# ESP32.net
KiCad netlist of a schematic drawn in Altium Designer
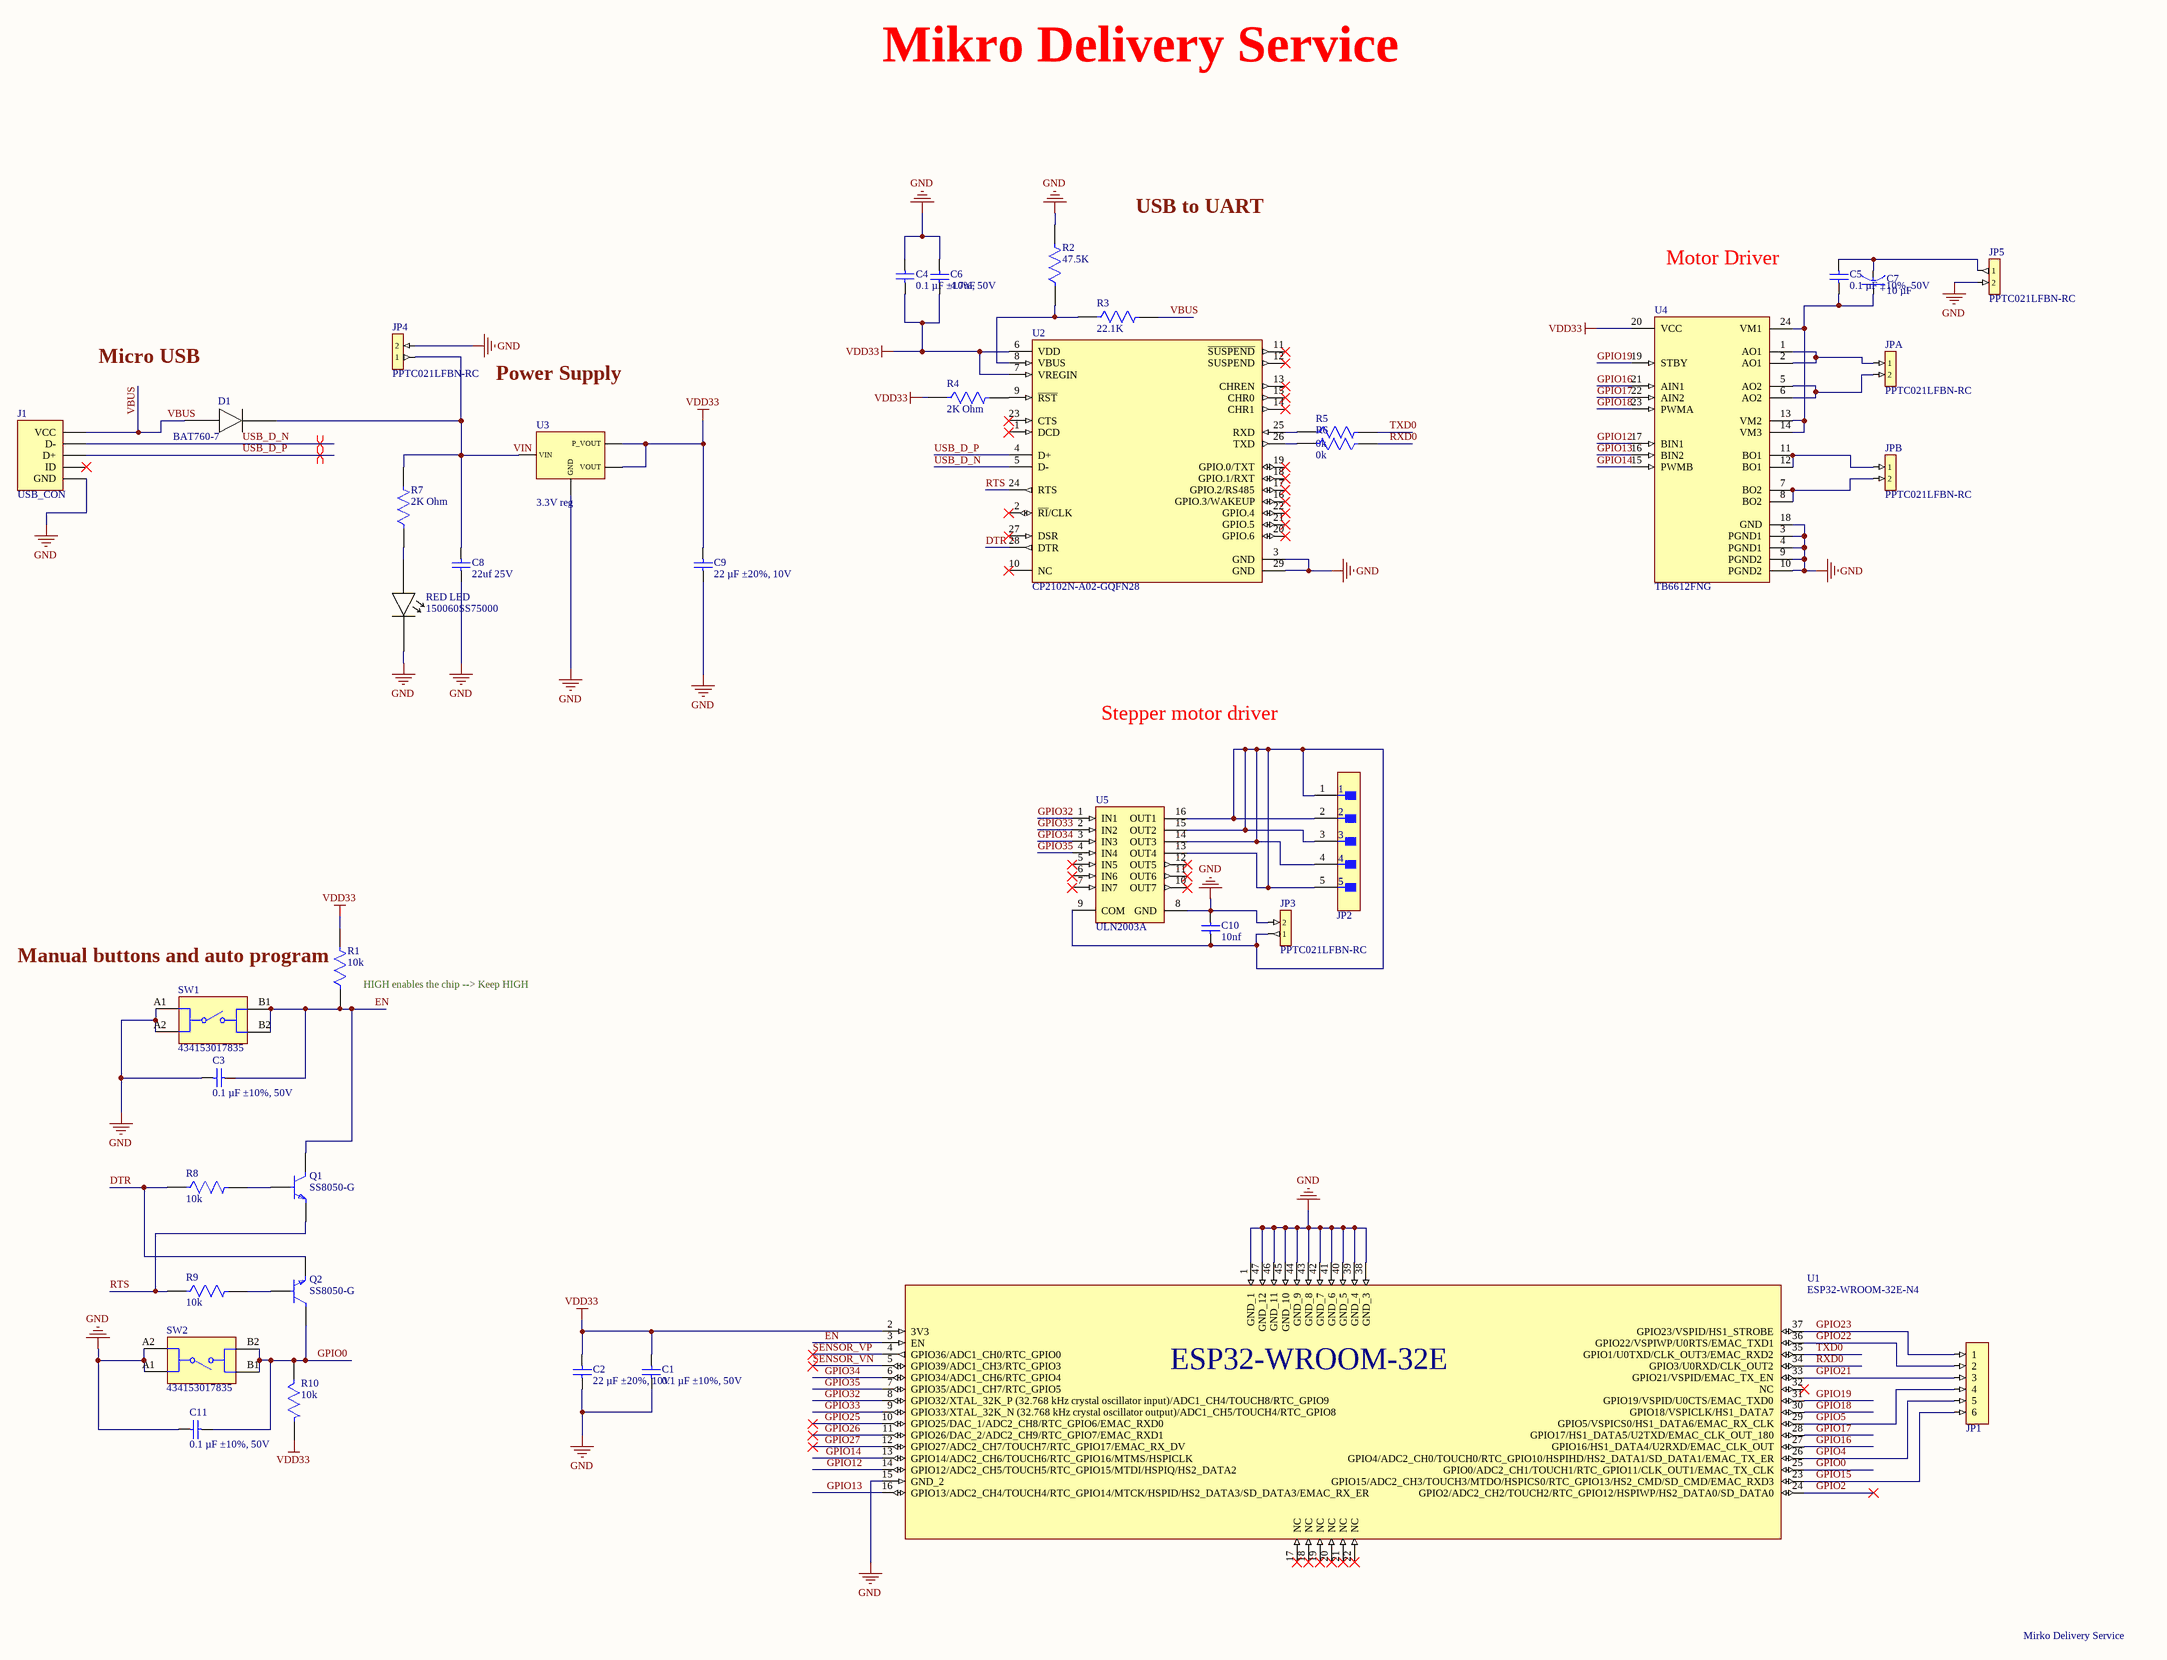
[diagram p0: ESP32.SchDoc]

(export (version "E")
  (design (tool "Eeschema 10.0.6"))
  (components
    (comp (ref "C1")
      (value "0.1 µF ±10%, 50V")
      (footprint "885012206095")
      (description "0.1 µF ±10% 50V Ceramic Capacitor X7R 0603 (1608 Metric)")
      (fields
        (field (name "MANUFACTURER") "Wurth Electronics")
        (field (name "MANUFACTURER PART NUMBER") "885012206095")
      )
      (libsource (lib "Schlib") (part "885012206095"))
    )
    (comp (ref "C2")
      (value "22 µF ±20%, 10V")
      (footprint "885012108011")
      (description "22 µF ±20% 10V Ceramic Capacitor X5R 1206 (3216 Metric)")
      (fields
        (field (name "MANUFACTURER") "Wurth Electronics")
        (field (name "MANUFACTURER PART NUMBER") "885012108011")
      )
      (libsource (lib "Schlib") (part "885012108011"))
    )
    (comp (ref "C3")
      (value "0.1 µF ±10%, 50V")
      (footprint "885012206095")
      (description "0.1 µF ±10% 50V Ceramic Capacitor X7R 0603 (1608 Metric)")
      (fields
        (field (name "MANUFACTURER") "Wurth Electronics")
        (field (name "MANUFACTURER PART NUMBER") "885012206095")
      )
      (libsource (lib "Schlib") (part "885012206095"))
    )
    (comp (ref "C4")
      (value "0.1 µF ±10%, 50V")
      (footprint "885012206095")
      (description "0.1 µF ±10% 50V Ceramic Capacitor X7R 0603 (1608 Metric)")
      (fields
        (field (name "MANUFACTURER") "Wurth Electronics")
        (field (name "MANUFACTURER PART NUMBER") "885012206095")
      )
      (libsource (lib "Schlib") (part "885012206095"))
    )
    (comp (ref "C5")
      (value "0.1 µF ±10%, 50V")
      (footprint "885012206095")
      (description "0.1 µF ±10% 50V Ceramic Capacitor X7R 0603 (1608 Metric)")
      (fields
        (field (name "MANUFACTURER") "Wurth Electronics")
        (field (name "MANUFACTURER PART NUMBER") "885012206095")
      )
      (libsource (lib "Schlib") (part "885012206095"))
    )
    (comp (ref "C6")
      (value "4.7uF")
      (footprint "FP-C0805C475J4RACAUTO-IPC_B")
      (description "4.7 µF ±5% 16V Ceramic Capacitor X7R 0805 (2012 Metric)")
      (fields
        (field (name "MANUFACTURER") "KEMET")
        (field (name "MANUFACTURER PART NUMBER") "C0805C475J4RACAUTO")
      )
      (libsource (lib "Schlib") (part "C0805C475J4RACAUTO"))
    )
    (comp (ref "C7")
      (value "10 µF")
      (footprint "FP-UWT1C100MCL1GB-MFG")
      (description "10 µF 16 V Aluminum Electrolytic Capacitors Radial, Can - SMD 1000 Hrs @ 105°C")
      (fields
        (field (name "MANUFACTURER") "Nichicon")
        (field (name "MANUFACTURER PART NUMBER") "UWT1C100MCL1GB")
      )
      (libsource (lib "Schlib") (part "UWT1C100MCL1GB"))
    )
    (comp (ref "C8")
      (value "22uf 25V")
      (footprint "CL31A226KAHNNNE")
      (description "22 µF ±10% 25V Ceramic Capacitor X5R 1206 (3216 Metric)")
      (fields
        (field (name "MANUFACTURER") "Samsung")
        (field (name "MANUFACTURER PART NUMBER") "CL31A226KAHNNNE")
      )
      (libsource (lib "Schlib") (part "CL31A226KAHNNNE"))
    )
    (comp (ref "C9")
      (value "22 µF ±20%, 10V")
      (footprint "885012108011")
      (description "22 µF ±20% 10V Ceramic Capacitor X5R 1206 (3216 Metric)")
      (fields
        (field (name "MANUFACTURER") "Wurth Electronics")
        (field (name "MANUFACTURER PART NUMBER") "885012108011")
      )
      (libsource (lib "Schlib") (part "885012108011"))
    )
    (comp (ref "C10")
      (value "10nf")
      (footprint "C0402C103K3REC7411")
      (description "10 nF ±10% 25V Ceramic Capacitor X7R 0402 (1005 Metric)")
      (fields
        (field (name "MANUFACTURER") "KEMET")
        (field (name "MANUFACTURER PART NUMBER") "C0402C103K3REC7411")
      )
      (libsource (lib "Schlib") (part "C0402C103K3REC7411"))
    )
    (comp (ref "C11")
      (value "0.1 µF ±10%, 50V")
      (footprint "885012206095")
      (description "0.1 µF ±10% 50V Ceramic Capacitor X7R 0603 (1608 Metric)")
      (fields
        (field (name "MANUFACTURER") "Wurth Electronics")
        (field (name "MANUFACTURER PART NUMBER") "885012206095")
      )
      (libsource (lib "Schlib") (part "885012206095"))
    )
    (comp (ref "D1")
      (value "BAT760-7")
      (footprint "BAT760-7")
      (description "Rectifier Diode, Schottky, 1 Phase, 1 Element, 1A, 30V V(RRM), Silicon")
      (fields (field (name "MANUFACTURER") "Diodes"))
      (libsource (lib "Schlib") (part "BAT760-7"))
    )
    (comp (ref "J1")
      (value "USB_CON")
      (footprint "10118192-0002LF")
      (description "Conn Micro USB 2.0 Type B RCP 5 POS 0.65mm Solder RA SMD 5 Terminal 1 Port T/R")
      (fields
        (field (name "MANUFACTURER") "Amphenol ICC / FCI")
        (field (name "MANUFACTURER PART NUMBER") "10118192-0002LF")
      )
      (libsource (lib "Schlib") (part "10118192-0002LF"))
    )
    (comp (ref "JP1")
      (value "PPPC061LFBN-RC")
      (footprint "PPPC061LFBN-RC")
      (fields (field (name "MANUFACTURER") "Sullins"))
      (libsource (lib "Schlib") (part "PPPC061LFBN-RC"))
    )
    (comp (ref "JP2")
      (value "B5B-XH-A")
      (footprint "FP-B5B-PH-K-S_LF_SN-MFG")
      (description "Connector Header Through Hole 5 position 0.098\" (2.50mm)")
      (fields (field (name "MANUFACTURER") "JST"))
      (libsource (lib "Schlib") (part "B5B-XH-A"))
    )
    (comp (ref "JP3")
      (value "PPTC021LFBN-RC")
      (footprint "PPTC021LFBN-RC")
      (description "2 Position Header Connector 0.100\" (2.54mm) Through Hole Tin")
      (fields (field (name "MANUFACTURER") "Sullins"))
      (libsource (lib "") (part "PPTC021LFBN-RC_3"))
    )
    (comp (ref "JP4")
      (value "PPTC021LFBN-RC")
      (footprint "PPTC021LFBN-RC")
      (description "2 Position Header Connector 0.100\" (2.54mm) Through Hole Tin")
      (fields (field (name "MANUFACTURER") "Sullins"))
      (libsource (lib "") (part "PPTC021LFBN-RC_2"))
    )
    (comp (ref "JP5")
      (value "PPTC021LFBN-RC")
      (footprint "PPTC021LFBN-RC")
      (description "2 Position Header Connector 0.100\" (2.54mm) Through Hole Tin")
      (fields (field (name "MANUFACTURER") "Sullins"))
      (libsource (lib "") (part "PPTC021LFBN-RC_1"))
    )
    (comp (ref "JPA")
      (value "PPTC021LFBN-RC")
      (footprint "PPTC021LFBN-RC")
      (description "2 Position Header Connector 0.100\" (2.54mm) Through Hole Tin")
      (fields (field (name "MANUFACTURER") "Sullins"))
      (libsource (lib "Schlib") (part "PPTC021LFBN-RC"))
    )
    (comp (ref "JPB")
      (value "PPTC021LFBN-RC")
      (footprint "PPTC021LFBN-RC")
      (description "2 Position Header Connector 0.100\" (2.54mm) Through Hole Tin")
      (fields (field (name "MANUFACTURER") "Sullins"))
      (libsource (lib "Schlib") (part "PPTC021LFBN-RC"))
    )
    (comp (ref "Q1")
      (value "SS8050-G")
      (footprint "FP-SS8050-G-IPC_B")
      (description "Bipolar (BJT) Transistor NPN 25 V 1.5 A 100MHz 300 mW Surface Mount SOT-23-3")
      (fields (field (name "MANUFACTURER") "Comchip"))
      (libsource (lib "Schlib") (part "SS8050-G"))
    )
    (comp (ref "Q2")
      (value "SS8050-G")
      (footprint "FP-SS8050-G-IPC_B")
      (description "Bipolar (BJT) Transistor NPN 25 V 1.5 A 100MHz 300 mW Surface Mount SOT-23-3")
      (fields (field (name "MANUFACTURER") "Comchip"))
      (libsource (lib "Schlib") (part "SS8050-G"))
    )
    (comp (ref "R1")
      (value "10k")
      (footprint "FP-RC0402-0_4-IPC_A")
      (description "10 kOhms ±5% 0.063W, 1/16W Chip Resistor 0402 (1005 Metric) Moisture Resistant Thick Film")
      (fields
        (field (name "MANUFACTURER") "Yageo")
        (field (name "MANUFACTURER PART NUMBER") "RC0402JR-0710KL")
      )
      (libsource (lib "Schlib") (part "RC0402JR-0710KL"))
    )
    (comp (ref "R2")
      (value "47.5K")
      (footprint "ERJ3EKF4752V")
      (description "47.5 kOhms ±1% 0.1W, 1/10W Chip Resistor 0603 (1608 Metric) Automotive AEC-Q200 Thick Film")
      (fields
        (field (name "MANUFACTURER") "Panasonic")
        (field (name "MANUFACTURER PART NUMBER") "ERJ-3EKF4752V")
      )
      (libsource (lib "Schlib") (part "ERJ-3EKF4752V"))
    )
    (comp (ref "R3")
      (value "22.1K")
      (footprint "RC0603FR-0722K1L")
      (description "22.1 kOhms ±1% 0.1W, 1/10W Chip Resistor 0603 (1608 Metric) Moisture Resistant Thick Film")
      (fields
        (field (name "MANUFACTURER") "Yageo")
        (field (name "MANUFACTURER PART NUMBER") "RC0603FR-0722K1L")
      )
      (libsource (lib "Schlib") (part "RC0603FR-0722K1L"))
    )
    (comp (ref "R4")
      (value "2K Ohm")
      (footprint "560112110015")
      (description "2 kOhms ±5% 0.1W, 1/10W Chip Resistor 0402 (1005 Metric) Anti-Sulfur Thick Film")
      (fields
        (field (name "MANUFACTURER") "Wurth Electronics")
        (field (name "MANUFACTURER PART NUMBER") "560112110015")
      )
      (libsource (lib "Schlib") (part "560112110015"))
    )
    (comp (ref "R5")
      (value "0k")
      (footprint "CR0402AJ/-000GAS")
      (fields
        (field (name "MANUFACTURER") "Bourns")
        (field (name "MANUFACTURER PART NUMBER") "CR0402AJ/-000GAS")
      )
      (libsource (lib "Schlib") (part "CR0402AJ/-000GAS"))
    )
    (comp (ref "R6")
      (value "0k")
      (footprint "CR0402AJ/-000GAS")
      (fields
        (field (name "MANUFACTURER") "Bourns")
        (field (name "MANUFACTURER PART NUMBER") "CR0402AJ/-000GAS")
      )
      (libsource (lib "Schlib") (part "CR0402AJ/-000GAS"))
    )
    (comp (ref "R7")
      (value "2K Ohm")
      (footprint "560112110015")
      (description "2 kOhms ±5% 0.1W, 1/10W Chip Resistor 0402 (1005 Metric) Anti-Sulfur Thick Film")
      (fields
        (field (name "MANUFACTURER") "Wurth Electronics")
        (field (name "MANUFACTURER PART NUMBER") "560112110015")
      )
      (libsource (lib "Schlib") (part "560112110015"))
    )
    (comp (ref "R8")
      (value "10k")
      (footprint "FP-RC0402-0_4-IPC_A")
      (description "10 kOhms ±5% 0.063W, 1/16W Chip Resistor 0402 (1005 Metric) Moisture Resistant Thick Film")
      (fields
        (field (name "MANUFACTURER") "Yageo")
        (field (name "MANUFACTURER PART NUMBER") "RC0402JR-0710KL")
      )
      (libsource (lib "Schlib") (part "RC0402JR-0710KL"))
    )
    (comp (ref "R9")
      (value "10k")
      (footprint "FP-RC0402-0_4-IPC_A")
      (description "10 kOhms ±5% 0.063W, 1/16W Chip Resistor 0402 (1005 Metric) Moisture Resistant Thick Film")
      (fields
        (field (name "MANUFACTURER") "Yageo")
        (field (name "MANUFACTURER PART NUMBER") "RC0402JR-0710KL")
      )
      (libsource (lib "Schlib") (part "RC0402JR-0710KL"))
    )
    (comp (ref "R10")
      (value "10k")
      (footprint "FP-RC0402-0_4-IPC_A")
      (description "10 kOhms ±5% 0.063W, 1/16W Chip Resistor 0402 (1005 Metric) Moisture Resistant Thick Film")
      (fields
        (field (name "MANUFACTURER") "Yageo")
        (field (name "MANUFACTURER PART NUMBER") "RC0402JR-0710KL")
      )
      (libsource (lib "Schlib") (part "RC0402JR-0710KL"))
    )
    (comp (ref "RED LED")
      (value "150060SS75000")
      (footprint "150060SS75000")
      (description "Red 630nm LED Indication - Discrete 1.9V 0603 (1608 Metric)")
      (fields (field (name "MANUFACTURER") "Wurth Electronics"))
      (libsource (lib "Schlib") (part "150060SS75000"))
    )
    (comp (ref "SW1")
      (value "434153017835")
      (footprint "434153017835")
      (fields (field (name "MANUFACTURER") "Wurth Electronics"))
      (libsource (lib "") (part "434153017835_1"))
    )
    (comp (ref "SW2")
      (value "434153017835")
      (footprint "434153017835")
      (fields (field (name "MANUFACTURER") "Wurth Electronics"))
      (libsource (lib "Schlib") (part "434153017835"))
    )
    (comp (ref "U1")
      (value "ESP32-WROOM-32E-N4")
      (footprint "FP-ESP32-WROOM-32E_4MB-MFG")
      (description "WiFi-Module 802.11/BT 2, 4-2, 5GHz 150Mb/s")
      (fields (field (name "MANUFACTURER") "Espressif Systems"))
      (libsource (lib "Schlib") (part "ESP32-WROOM-32E-N4"))
    )
    (comp (ref "U2")
      (value "CP2102N-A02-GQFN28")
      (footprint "FP-CP2102N-A02-GQFN28-IPC_C")
      (description "USB Bridge, USB to UART USB 2.0 UART Interface 28-QFN (5x5)")
      (fields (field (name "MANUFACTURER") "Silicon Labs"))
      (libsource (lib "Schlib") (part "CP2102N-A02-GQFN28"))
    )
    (comp (ref "U3")
      (value "3.3V reg")
      (footprint "AMS1117-3.3")
      (description "Linear Voltage Regulator IC Positive Fixed 1 Output 1A SOT-223-3L")
      (fields (field (name "MANUFACTURER") "Revvo") (field (name "MANUFACTURER PART NUMBER") "AMS1117-3.3"))
      (libsource (lib "Schlib") (part "AMS1117-3.3"))
    )
    (comp (ref "U4")
      (value "TB6612FNG")
      (footprint "FP-SSOP24-P-300-0_65A-IPC_B")
      (description "Brushless DC Motor Controller, 1A, BCDMOS, PDSO24")
      (fields
        (field (name "MANUFACTURER") "Toshiba")
        (field (name "MANUFACTURER PART NUMBER") "TB6612FNG,C,8,EL")
      )
      (libsource (lib "Schlib") (part "TB6612FNG,C,8,EL"))
    )
    (comp (ref "U5")
      (value "ULN2003A")
      (footprint "STM-DIP-16L")
      (description "Bipolar (BJT) Transistor Array Through Hole 16-DIP")
      (fields (field (name "MANUFACTURER") "STMicroelectronics"))
      (libsource (lib "Schlib") (part "ULN2003A"))
    )
  )
  (nets
    (net (code "1") (name "/DTR") (class "Default")
      (node (ref "Q2") (pin "2") (pinfunction "E_2") (pintype "passive"))
      (node (ref "R8") (pin "1") (pinfunction "1_1") (pintype "passive"))
      (node (ref "U2") (pin "28") (pinfunction "DTR_28") (pintype "output"))
    )
    (net (code "2") (name "/EN") (class "Default")
      (node (ref "C3") (pin "2") (pinfunction "2_2") (pintype "passive"))
      (node (ref "Q1") (pin "3") (pinfunction "C_3") (pintype "passive"))
      (node (ref "R1") (pin "1") (pinfunction "1_1") (pintype "passive"))
      (node (ref "SW1") (pin "B1") (pinfunction "B1_B1") (pintype "passive"))
      (node (ref "SW1") (pin "B2") (pinfunction "B2_B2") (pintype "passive"))
      (node (ref "U1") (pin "3") (pinfunction "EN_3") (pintype "input"))
    )
    (net (code "3") (name "/GPIO0") (class "Default")
      (node (ref "C11") (pin "2") (pinfunction "2_2") (pintype "passive"))
      (node (ref "Q2") (pin "3") (pinfunction "C_3") (pintype "passive"))
      (node (ref "R10") (pin "1") (pinfunction "1_1") (pintype "passive"))
      (node (ref "SW2") (pin "B1") (pinfunction "B1_B1") (pintype "passive"))
      (node (ref "SW2") (pin "B2") (pinfunction "B2_B2") (pintype "passive"))
      (node (ref "U1") (pin "25") (pinfunction "GPIO0/ADC2_CH1/TOUCH1/RTC_GPIO11/CLK_OUT1/EMAC_TX_CLK_25") (pintype "bidirectional"))
    )
    (net (code "4") (name "/GPIO2") (class "Default")
      (node (ref "U1") (pin "24") (pinfunction "GPIO2/ADC2_CH2/TOUCH2/RTC_GPIO12/HSPIWP/HS2_DATA0/SD_DATA0_24") (pintype "bidirectional+no_connect"))
    )
    (net (code "5") (name "/GPIO4") (class "Default")
      (node (ref "JP1") (pin "5") (pinfunction "5_5") (pintype "input"))
      (node (ref "U1") (pin "26") (pinfunction "GPIO4/ADC2_CH0/TOUCH0/RTC_GPIO10/HSPIHD/HS2_DATA1/SD_DATA1/EMAC_TX_ER_26") (pintype "bidirectional"))
    )
    (net (code "6") (name "/GPIO5") (class "Default")
      (node (ref "JP1") (pin "4") (pinfunction "4_4") (pintype "input"))
      (node (ref "U1") (pin "29") (pinfunction "GPIO5/VSPICS0/HS1_DATA6/EMAC_RX_CLK_29") (pintype "bidirectional"))
    )
    (net (code "7") (name "/GPIO12") (class "Default")
      (node (ref "U1") (pin "14") (pinfunction "GPIO12/ADC2_CH5/TOUCH5/RTC_GPIO15/MTDI/HSPIQ/HS2_DATA2_14") (pintype "bidirectional"))
      (node (ref "U4") (pin "17") (pinfunction "BIN1_17") (pintype "input"))
    )
    (net (code "8") (name "/GPIO13") (class "Default")
      (node (ref "U1") (pin "16") (pinfunction "GPIO13/ADC2_CH4/TOUCH4/RTC_GPIO14/MTCK/HSPID/HS2_DATA3/SD_DATA3/EMAC_RX_ER_16") (pintype "bidirectional"))
      (node (ref "U4") (pin "16") (pinfunction "BIN2_16") (pintype "input"))
    )
    (net (code "9") (name "/GPIO14") (class "Default")
      (node (ref "U1") (pin "13") (pinfunction "GPIO14/ADC2_CH6/TOUCH6/RTC_GPIO16/MTMS/HSPICLK_13") (pintype "bidirectional"))
      (node (ref "U4") (pin "15") (pinfunction "PWMB_15") (pintype "input"))
    )
    (net (code "10") (name "/GPIO15") (class "Default")
      (node (ref "JP1") (pin "6") (pinfunction "6_6") (pintype "input"))
      (node (ref "U1") (pin "23") (pinfunction "GPIO15/ADC2_CH3/TOUCH3/MTDO/HSPICS0/RTC_GPIO13/HS2_CMD/SD_CMD/EMAC_RXD3_23") (pintype "bidirectional"))
    )
    (net (code "11") (name "/GPIO16") (class "Default")
      (node (ref "U1") (pin "27") (pinfunction "GPIO16/HS1_DATA4/U2RXD/EMAC_CLK_OUT_27") (pintype "bidirectional"))
      (node (ref "U4") (pin "21") (pinfunction "AIN1_21") (pintype "input"))
    )
    (net (code "12") (name "/GPIO17") (class "Default")
      (node (ref "U1") (pin "28") (pinfunction "GPIO17/HS1_DATA5/U2TXD/EMAC_CLK_OUT_180_28") (pintype "bidirectional"))
      (node (ref "U4") (pin "22") (pinfunction "AIN2_22") (pintype "input"))
    )
    (net (code "13") (name "/GPIO18") (class "Default")
      (node (ref "U1") (pin "30") (pinfunction "GPIO18/VSPICLK/HS1_DATA7_30") (pintype "bidirectional"))
      (node (ref "U4") (pin "23") (pinfunction "PWMA_23") (pintype "input"))
    )
    (net (code "14") (name "/GPIO19") (class "Default")
      (node (ref "U1") (pin "31") (pinfunction "GPIO19/VSPID/U0CTS/EMAC_TXD0_31") (pintype "bidirectional"))
      (node (ref "U4") (pin "19") (pinfunction "STBY_19") (pintype "input"))
    )
    (net (code "15") (name "/GPIO21") (class "Default")
      (node (ref "JP1") (pin "3") (pinfunction "3_3") (pintype "input"))
      (node (ref "U1") (pin "33") (pinfunction "GPIO21/VSPID/EMAC_TX_EN_33") (pintype "bidirectional"))
    )
    (net (code "16") (name "/GPIO22") (class "Default")
      (node (ref "JP1") (pin "2") (pinfunction "2_2") (pintype "input"))
      (node (ref "U1") (pin "36") (pinfunction "GPIO22/VSPIWP/U0RTS/EMAC_TXD1_36") (pintype "bidirectional"))
    )
    (net (code "17") (name "/GPIO23") (class "Default")
      (node (ref "JP1") (pin "1") (pinfunction "1_1") (pintype "input"))
      (node (ref "U1") (pin "37") (pinfunction "GPIO23/VSPID/HS1_STROBE_37") (pintype "bidirectional"))
    )
    (net (code "18") (name "/GPIO25") (class "Default")
      (node (ref "U1") (pin "10") (pinfunction "GPIO25/DAC_1/ADC2_CH8/RTC_GPIO6/EMAC_RXD0_10") (pintype "bidirectional+no_connect"))
    )
    (net (code "19") (name "/GPIO26") (class "Default")
      (node (ref "U1") (pin "11") (pinfunction "GPIO26/DAC_2/ADC2_CH9/RTC_GPIO7/EMAC_RXD1_11") (pintype "bidirectional+no_connect"))
    )
    (net (code "20") (name "/GPIO27") (class "Default")
      (node (ref "U1") (pin "12") (pinfunction "GPIO27/ADC2_CH7/TOUCH7/RTC_GPIO17/EMAC_RX_DV_12") (pintype "bidirectional+no_connect"))
    )
    (net (code "21") (name "/GPIO32") (class "Default")
      (node (ref "U1") (pin "8") (pinfunction "GPIO32/XTAL_32K_P_(32.768_kHz_crystal_oscillator_input)/ADC1_CH4/TOUCH8/RTC_GPIO9_8") (pintype "bidirectional"))
      (node (ref "U5") (pin "1") (pinfunction "IN1_1") (pintype "input"))
    )
    (net (code "22") (name "/GPIO33") (class "Default")
      (node (ref "U1") (pin "9") (pinfunction "GPIO33/XTAL_32K_N_(32.768_kHz_crystal_oscillator_output)/ADC1_CH5/TOUCH4/RTC_GPIO8_9") (pintype "bidirectional"))
      (node (ref "U5") (pin "2") (pinfunction "IN2_2") (pintype "input"))
    )
    (net (code "23") (name "/GPIO34") (class "Default")
      (node (ref "U1") (pin "6") (pinfunction "GPIO34/ADC1_CH6/RTC_GPIO4_6") (pintype "bidirectional"))
      (node (ref "U5") (pin "3") (pinfunction "IN3_3") (pintype "input"))
    )
    (net (code "24") (name "/GPIO35") (class "Default")
      (node (ref "U1") (pin "7") (pinfunction "GPIO35/ADC1_CH7/RTC_GPIO5_7") (pintype "bidirectional"))
      (node (ref "U5") (pin "4") (pinfunction "IN4_4") (pintype "input"))
    )
    (net (code "25") (name "/RTS") (class "Default")
      (node (ref "Q1") (pin "2") (pinfunction "E_2") (pintype "passive"))
      (node (ref "R9") (pin "1") (pinfunction "1_1") (pintype "passive"))
      (node (ref "U2") (pin "24") (pinfunction "RTS_24") (pintype "output"))
    )
    (net (code "26") (name "/RXD0") (class "Default")
      (node (ref "R6") (pin "1") (pinfunction "1_1") (pintype "passive"))
      (node (ref "U1") (pin "34") (pinfunction "GPIO3/U0RXD/CLK_OUT2_34") (pintype "bidirectional"))
    )
    (net (code "27") (name "/SENSOR_VN") (class "Default")
      (node (ref "U1") (pin "5") (pinfunction "GPIO39/ADC1_CH3/RTC_GPIO3_5") (pintype "bidirectional+no_connect"))
    )
    (net (code "28") (name "/SENSOR_VP") (class "Default")
      (node (ref "U1") (pin "4") (pinfunction "GPIO36/ADC1_CH0/RTC_GPIO0_4") (pintype "output+no_connect"))
    )
    (net (code "29") (name "/TXD0") (class "Default")
      (node (ref "R5") (pin "2") (pinfunction "2_2") (pintype "passive"))
      (node (ref "U1") (pin "35") (pinfunction "GPIO1/U0TXD/CLK_OUT3/EMAC_RXD2_35") (pintype "bidirectional"))
    )
    (net (code "30") (name "/USB_D_N") (class "Default")
      (node (ref "J1") (pin "2") (pinfunction "D-_2") (pintype "passive"))
      (node (ref "U2") (pin "5") (pinfunction "D-_5") (pintype "passive"))
    )
    (net (code "31") (name "/USB_D_P") (class "Default")
      (node (ref "J1") (pin "3") (pinfunction "D+_3") (pintype "passive"))
      (node (ref "U2") (pin "4") (pinfunction "D+_4") (pintype "passive"))
    )
    (net (code "32") (name "/VBUS") (class "Default")
      (node (ref "D1") (pin "0") (pinfunction "0_0") (pintype "passive"))
      (node (ref "J1") (pin "1") (pinfunction "VCC_1") (pintype "passive"))
      (node (ref "R3") (pin "2") (pinfunction "2_2") (pintype "passive"))
    )
    (net (code "33") (name "/VIN") (class "Default")
      (node (ref "C8") (pin "2") (pinfunction "2_2") (pintype "passive"))
      (node (ref "D1") (pin "1") (pinfunction "1_1") (pintype "passive"))
      (node (ref "JP4") (pin "9") (pinfunction "1_9") (pintype "output"))
      (node (ref "R7") (pin "2") (pinfunction "2_2") (pintype "passive"))
      (node (ref "U3") (pin "6") (pinfunction "VIN_6") (pintype "passive"))
    )
    (net (code "34") (name "GND") (class "Default")
      (node (ref "C1") (pin "1") (pinfunction "1_1") (pintype "passive"))
      (node (ref "C10") (pin "2") (pinfunction "2_2") (pintype "passive"))
      (node (ref "C11") (pin "1") (pinfunction "1_1") (pintype "passive"))
      (node (ref "C2") (pin "1") (pinfunction "1_1") (pintype "passive"))
      (node (ref "C3") (pin "1") (pinfunction "1_1") (pintype "passive"))
      (node (ref "C4") (pin "1") (pinfunction "1_1") (pintype "passive"))
      (node (ref "C6") (pin "2") (pinfunction "2_2") (pintype "passive"))
      (node (ref "C8") (pin "1") (pinfunction "1_1") (pintype "passive"))
      (node (ref "C9") (pin "1") (pinfunction "1_1") (pintype "passive"))
      (node (ref "J1") (pin "5") (pinfunction "GND_5") (pintype "passive"))
      (node (ref "JP3") (pin "2") (pinfunction "2_2") (pintype "input"))
      (node (ref "JP4") (pin "2") (pinfunction "2_2") (pintype "input"))
      (node (ref "JP5") (pin "2") (pinfunction "2_2") (pintype "input"))
      (node (ref "R2") (pin "2") (pinfunction "2_2") (pintype "passive"))
      (node (ref "RED LED") (pin "1") (pinfunction "1_1") (pintype "passive"))
      (node (ref "SW1") (pin "A1") (pinfunction "A1_A1") (pintype "passive"))
      (node (ref "SW1") (pin "A2") (pinfunction "A2_A2") (pintype "passive"))
      (node (ref "SW2") (pin "A1") (pinfunction "A1_A1") (pintype "passive"))
      (node (ref "SW2") (pin "A2") (pinfunction "A2_A2") (pintype "passive"))
      (node (ref "U1") (pin "1") (pinfunction "GND_1_1") (pintype "input"))
      (node (ref "U1") (pin "15") (pinfunction "GND_2_15") (pintype "input"))
      (node (ref "U1") (pin "38") (pinfunction "GND_3_38") (pintype "input"))
      (node (ref "U1") (pin "39") (pinfunction "GND_4_39") (pintype "input"))
      (node (ref "U1") (pin "40") (pinfunction "GND_5_40") (pintype "input"))
      (node (ref "U1") (pin "41") (pinfunction "GND_6_41") (pintype "input"))
      (node (ref "U1") (pin "42") (pinfunction "GND_7_42") (pintype "input"))
      (node (ref "U1") (pin "43") (pinfunction "GND_8_43") (pintype "input"))
      (node (ref "U1") (pin "44") (pinfunction "GND_9_44") (pintype "input"))
      (node (ref "U1") (pin "45") (pinfunction "GND_10_45") (pintype "input"))
      (node (ref "U1") (pin "46") (pinfunction "GND_11_46") (pintype "input"))
      (node (ref "U1") (pin "47") (pinfunction "GND_12_47") (pintype "input"))
      (node (ref "U2") (pin "29") (pinfunction "GND_29") (pintype "power_in"))
      (node (ref "U2") (pin "3") (pinfunction "GND_3") (pintype "power_in"))
      (node (ref "U3") (pin "3") (pinfunction "GND_3") (pintype "passive"))
      (node (ref "U4") (pin "10") (pinfunction "PGND2_10") (pintype "power_in"))
      (node (ref "U4") (pin "18") (pinfunction "GND_18") (pintype "power_in"))
      (node (ref "U4") (pin "3") (pinfunction "PGND1_3") (pintype "power_in"))
      (node (ref "U4") (pin "4") (pinfunction "PGND1_4") (pintype "power_in"))
      (node (ref "U4") (pin "9") (pinfunction "PGND2_9") (pintype "power_in"))
      (node (ref "U5") (pin "8") (pinfunction "GND_8") (pintype "power_in"))
    )
    (net (code "35") (name "Net-(C7-A)") (class "Default")
      (node (ref "C5") (pin "1") (pinfunction "1_1") (pintype "passive"))
      (node (ref "C7") (pin "2") (pinfunction "A_2") (pintype "passive"))
      (node (ref "U4") (pin "13") (pinfunction "VM2_13") (pintype "power_in"))
      (node (ref "U4") (pin "14") (pinfunction "VM3_14") (pintype "power_in"))
      (node (ref "U4") (pin "24") (pinfunction "VM1_24") (pintype "power_in"))
    )
    (net (code "36") (name "Net-(C7-C)") (class "Default")
      (node (ref "C5") (pin "2") (pinfunction "2_2") (pintype "passive"))
      (node (ref "C7") (pin "1") (pinfunction "C_1") (pintype "passive"))
      (node (ref "JP5") (pin "9") (pinfunction "1_9") (pintype "output"))
    )
    (net (code "37") (name "Net-(JP3-1)") (class "Default")
      (node (ref "C10") (pin "1") (pinfunction "1_1") (pintype "passive"))
      (node (ref "JP2") (pin "1") (pinfunction "1_1") (pintype "passive"))
      (node (ref "JP2") (pin "2") (pinfunction "2_2") (pintype "passive"))
      (node (ref "JP2") (pin "3") (pinfunction "3_3") (pintype "passive"))
      (node (ref "JP2") (pin "4") (pinfunction "4_4") (pintype "passive"))
      (node (ref "JP2") (pin "5") (pinfunction "5_5") (pintype "passive"))
      (node (ref "JP3") (pin "9") (pinfunction "1_9") (pintype "output"))
      (node (ref "U5") (pin "13") (pinfunction "OUT4_13") (pintype "passive"))
      (node (ref "U5") (pin "14") (pinfunction "OUT3_14") (pintype "passive"))
      (node (ref "U5") (pin "15") (pinfunction "OUT2_15") (pintype "passive"))
      (node (ref "U5") (pin "16") (pinfunction "OUT1_16") (pintype "passive"))
      (node (ref "U5") (pin "9") (pinfunction "COM_9") (pintype "passive"))
    )
    (net (code "38") (name "Net-(JPA-1)") (class "Default")
      (node (ref "JPA") (pin "9") (pinfunction "1_9") (pintype "input"))
      (node (ref "U4") (pin "1") (pinfunction "AO1_1") (pintype "passive"))
      (node (ref "U4") (pin "2") (pinfunction "AO1_2") (pintype "passive"))
    )
    (net (code "39") (name "Net-(JPA-Pad2)") (class "Default")
      (node (ref "JPA") (pin "2") (pinfunction "2_2") (pintype "input"))
      (node (ref "U4") (pin "5") (pinfunction "AO2_5") (pintype "passive"))
      (node (ref "U4") (pin "6") (pinfunction "AO2_6") (pintype "passive"))
    )
    (net (code "40") (name "Net-(JPB-1)") (class "Default")
      (node (ref "JPB") (pin "9") (pinfunction "1_9") (pintype "input"))
      (node (ref "U4") (pin "11") (pinfunction "BO1_11") (pintype "passive"))
      (node (ref "U4") (pin "12") (pinfunction "BO1_12") (pintype "passive"))
    )
    (net (code "41") (name "Net-(JPB-Pad2)") (class "Default")
      (node (ref "JPB") (pin "2") (pinfunction "2_2") (pintype "input"))
      (node (ref "U4") (pin "7") (pinfunction "BO2_7") (pintype "passive"))
      (node (ref "U4") (pin "8") (pinfunction "BO2_8") (pintype "passive"))
    )
    (net (code "42") (name "Net-(Q1-B)") (class "Default")
      (node (ref "Q1") (pin "1") (pinfunction "B_1") (pintype "passive"))
      (node (ref "R8") (pin "2") (pinfunction "2_2") (pintype "passive"))
    )
    (net (code "43") (name "Net-(Q2-B)") (class "Default")
      (node (ref "Q2") (pin "1") (pinfunction "B_1") (pintype "passive"))
      (node (ref "R9") (pin "2") (pinfunction "2_2") (pintype "passive"))
    )
    (net (code "44") (name "Net-(R7-Pad1)") (class "Default")
      (node (ref "R7") (pin "1") (pinfunction "1_1") (pintype "passive"))
      (node (ref "RED LED") (pin "0") (pinfunction "0_0") (pintype "passive"))
    )
    (net (code "45") (name "Net-(U2-RXD)") (class "Default")
      (node (ref "R5") (pin "1") (pinfunction "1_1") (pintype "passive"))
      (node (ref "U2") (pin "25") (pinfunction "RXD_25") (pintype "input"))
    )
    (net (code "46") (name "Net-(U2-TXD)") (class "Default")
      (node (ref "R6") (pin "2") (pinfunction "2_2") (pintype "passive"))
      (node (ref "U2") (pin "26") (pinfunction "TXD_26") (pintype "output"))
    )
    (net (code "47") (name "Net-(U2-VBUS)") (class "Default")
      (node (ref "R2") (pin "1") (pinfunction "1_1") (pintype "passive"))
      (node (ref "R3") (pin "1") (pinfunction "1_1") (pintype "passive"))
      (node (ref "U2") (pin "8") (pinfunction "VBUS_8") (pintype "input"))
    )
    (net (code "48") (name "Net-(U2-~{RST})") (class "Default")
      (node (ref "R4") (pin "2") (pinfunction "2_2") (pintype "passive"))
      (node (ref "U2") (pin "9") (pinfunction "~{RST}_9") (pintype "input"))
    )
    (net (code "49") (name "VDD33") (class "Default")
      (node (ref "C1") (pin "2") (pinfunction "2_2") (pintype "passive"))
      (node (ref "C2") (pin "2") (pinfunction "2_2") (pintype "passive"))
      (node (ref "C4") (pin "2") (pinfunction "2_2") (pintype "passive"))
      (node (ref "C6") (pin "1") (pinfunction "1_1") (pintype "passive"))
      (node (ref "C9") (pin "2") (pinfunction "2_2") (pintype "passive"))
      (node (ref "R1") (pin "2") (pinfunction "2_2") (pintype "passive"))
      (node (ref "R10") (pin "2") (pinfunction "2_2") (pintype "passive"))
      (node (ref "R4") (pin "1") (pinfunction "1_1") (pintype "passive"))
      (node (ref "U1") (pin "2") (pinfunction "3V3_2") (pintype "input"))
      (node (ref "U2") (pin "6") (pinfunction "VDD_6") (pintype "power_in"))
      (node (ref "U2") (pin "7") (pinfunction "VREGIN_7") (pintype "input"))
      (node (ref "U3") (pin "4") (pinfunction "VOUT_4") (pintype "passive"))
      (node (ref "U3") (pin "5") (pinfunction "P_VOUT_5") (pintype "passive"))
      (node (ref "U4") (pin "20") (pinfunction "VCC_20") (pintype "power_in"))
    )
    (net (code "50") (name "unconnected-(J1-ID-Pad4)") (class "Default")
      (node (ref "J1") (pin "4") (pinfunction "ID_4") (pintype "passive+no_connect"))
    )
    (net (code "51") (name "unconnected-(U1-NC-Pad17)") (class "Default")
      (node (ref "U1") (pin "17") (pinfunction "NC_17") (pintype "input+no_connect"))
    )
    (net (code "52") (name "unconnected-(U1-NC-Pad18)") (class "Default")
      (node (ref "U1") (pin "18") (pinfunction "NC_18") (pintype "input+no_connect"))
    )
    (net (code "53") (name "unconnected-(U1-NC-Pad19)") (class "Default")
      (node (ref "U1") (pin "19") (pinfunction "NC_19") (pintype "input+no_connect"))
    )
    (net (code "54") (name "unconnected-(U1-NC-Pad20)") (class "Default")
      (node (ref "U1") (pin "20") (pinfunction "NC_20") (pintype "input+no_connect"))
    )
    (net (code "55") (name "unconnected-(U1-NC-Pad21)") (class "Default")
      (node (ref "U1") (pin "21") (pinfunction "NC_21") (pintype "input+no_connect"))
    )
    (net (code "56") (name "unconnected-(U1-NC-Pad22)") (class "Default")
      (node (ref "U1") (pin "22") (pinfunction "NC_22") (pintype "input+no_connect"))
    )
    (net (code "57") (name "unconnected-(U1-NC-Pad32)") (class "Default")
      (node (ref "U1") (pin "32") (pinfunction "NC_32") (pintype "bidirectional+no_connect"))
    )
    (net (code "58") (name "unconnected-(U2-CHR0-Pad15)") (class "Default")
      (node (ref "U2") (pin "15") (pinfunction "CHR0_15") (pintype "output+no_connect"))
    )
    (net (code "59") (name "unconnected-(U2-CHR1-Pad14)") (class "Default")
      (node (ref "U2") (pin "14") (pinfunction "CHR1_14") (pintype "output+no_connect"))
    )
    (net (code "60") (name "unconnected-(U2-CHREN-Pad13)") (class "Default")
      (node (ref "U2") (pin "13") (pinfunction "CHREN_13") (pintype "output+no_connect"))
    )
    (net (code "61") (name "unconnected-(U2-CTS-Pad23)") (class "Default")
      (node (ref "U2") (pin "23") (pinfunction "CTS_23") (pintype "input+no_connect"))
    )
    (net (code "62") (name "unconnected-(U2-DCD-Pad1)") (class "Default")
      (node (ref "U2") (pin "1") (pinfunction "DCD_1") (pintype "input+no_connect"))
    )
    (net (code "63") (name "unconnected-(U2-DSR-Pad27)") (class "Default")
      (node (ref "U2") (pin "27") (pinfunction "DSR_27") (pintype "input+no_connect"))
    )
    (net (code "64") (name "unconnected-(U2-GPIO.0{slash}TXT-Pad19)") (class "Default")
      (node (ref "U2") (pin "19") (pinfunction "GPIO.0/TXT_19") (pintype "bidirectional+no_connect"))
    )
    (net (code "65") (name "unconnected-(U2-GPIO.1{slash}RXT-Pad18)") (class "Default")
      (node (ref "U2") (pin "18") (pinfunction "GPIO.1/RXT_18") (pintype "bidirectional+no_connect"))
    )
    (net (code "66") (name "unconnected-(U2-GPIO.2{slash}RS485-Pad17)") (class "Default")
      (node (ref "U2") (pin "17") (pinfunction "GPIO.2/RS485_17") (pintype "bidirectional+no_connect"))
    )
    (net (code "67") (name "unconnected-(U2-GPIO.3{slash}WAKEUP-Pad16)") (class "Default")
      (node (ref "U2") (pin "16") (pinfunction "GPIO.3/WAKEUP_16") (pintype "bidirectional+no_connect"))
    )
    (net (code "68") (name "unconnected-(U2-GPIO.4-Pad22)") (class "Default")
      (node (ref "U2") (pin "22") (pinfunction "GPIO.4_22") (pintype "bidirectional+no_connect"))
    )
    (net (code "69") (name "unconnected-(U2-GPIO.5-Pad21)") (class "Default")
      (node (ref "U2") (pin "21") (pinfunction "GPIO.5_21") (pintype "bidirectional+no_connect"))
    )
    (net (code "70") (name "unconnected-(U2-GPIO.6-Pad20)") (class "Default")
      (node (ref "U2") (pin "20") (pinfunction "GPIO.6_20") (pintype "bidirectional+no_connect"))
    )
    (net (code "71") (name "unconnected-(U2-NC-Pad10)") (class "Default")
      (node (ref "U2") (pin "10") (pinfunction "NC_10") (pintype "passive+no_connect"))
    )
    (net (code "72") (name "unconnected-(U2-SUSPEND-Pad12)") (class "Default")
      (node (ref "U2") (pin "12") (pinfunction "SUSPEND_12") (pintype "output+no_connect"))
    )
    (net (code "73") (name "unconnected-(U2-~{RI}{slash}CLK-Pad2)") (class "Default")
      (node (ref "U2") (pin "2") (pinfunction "~{RI}/CLK_2") (pintype "bidirectional+no_connect"))
    )
    (net (code "74") (name "unconnected-(U2-~{SUSPEND}-Pad11)") (class "Default")
      (node (ref "U2") (pin "11") (pinfunction "~{SUSPEND}_11") (pintype "output+no_connect"))
    )
    (net (code "75") (name "unconnected-(U5-IN5-Pad5)") (class "Default")
      (node (ref "U5") (pin "5") (pinfunction "IN5_5") (pintype "input+no_connect"))
    )
    (net (code "76") (name "unconnected-(U5-IN6-Pad6)") (class "Default")
      (node (ref "U5") (pin "6") (pinfunction "IN6_6") (pintype "input+no_connect"))
    )
    (net (code "77") (name "unconnected-(U5-IN7-Pad7)") (class "Default")
      (node (ref "U5") (pin "7") (pinfunction "IN7_7") (pintype "input+no_connect"))
    )
    (net (code "78") (name "unconnected-(U5-OUT5-Pad12)") (class "Default")
      (node (ref "U5") (pin "12") (pinfunction "OUT5_12") (pintype "output+no_connect"))
    )
    (net (code "79") (name "unconnected-(U5-OUT6-Pad11)") (class "Default")
      (node (ref "U5") (pin "11") (pinfunction "OUT6_11") (pintype "output+no_connect"))
    )
    (net (code "80") (name "unconnected-(U5-OUT7-Pad10)") (class "Default")
      (node (ref "U5") (pin "10") (pinfunction "OUT7_10") (pintype "output+no_connect"))
    )
  )
)
